# tx.net
KiCad netlist of a schematic drawn in EAGLE
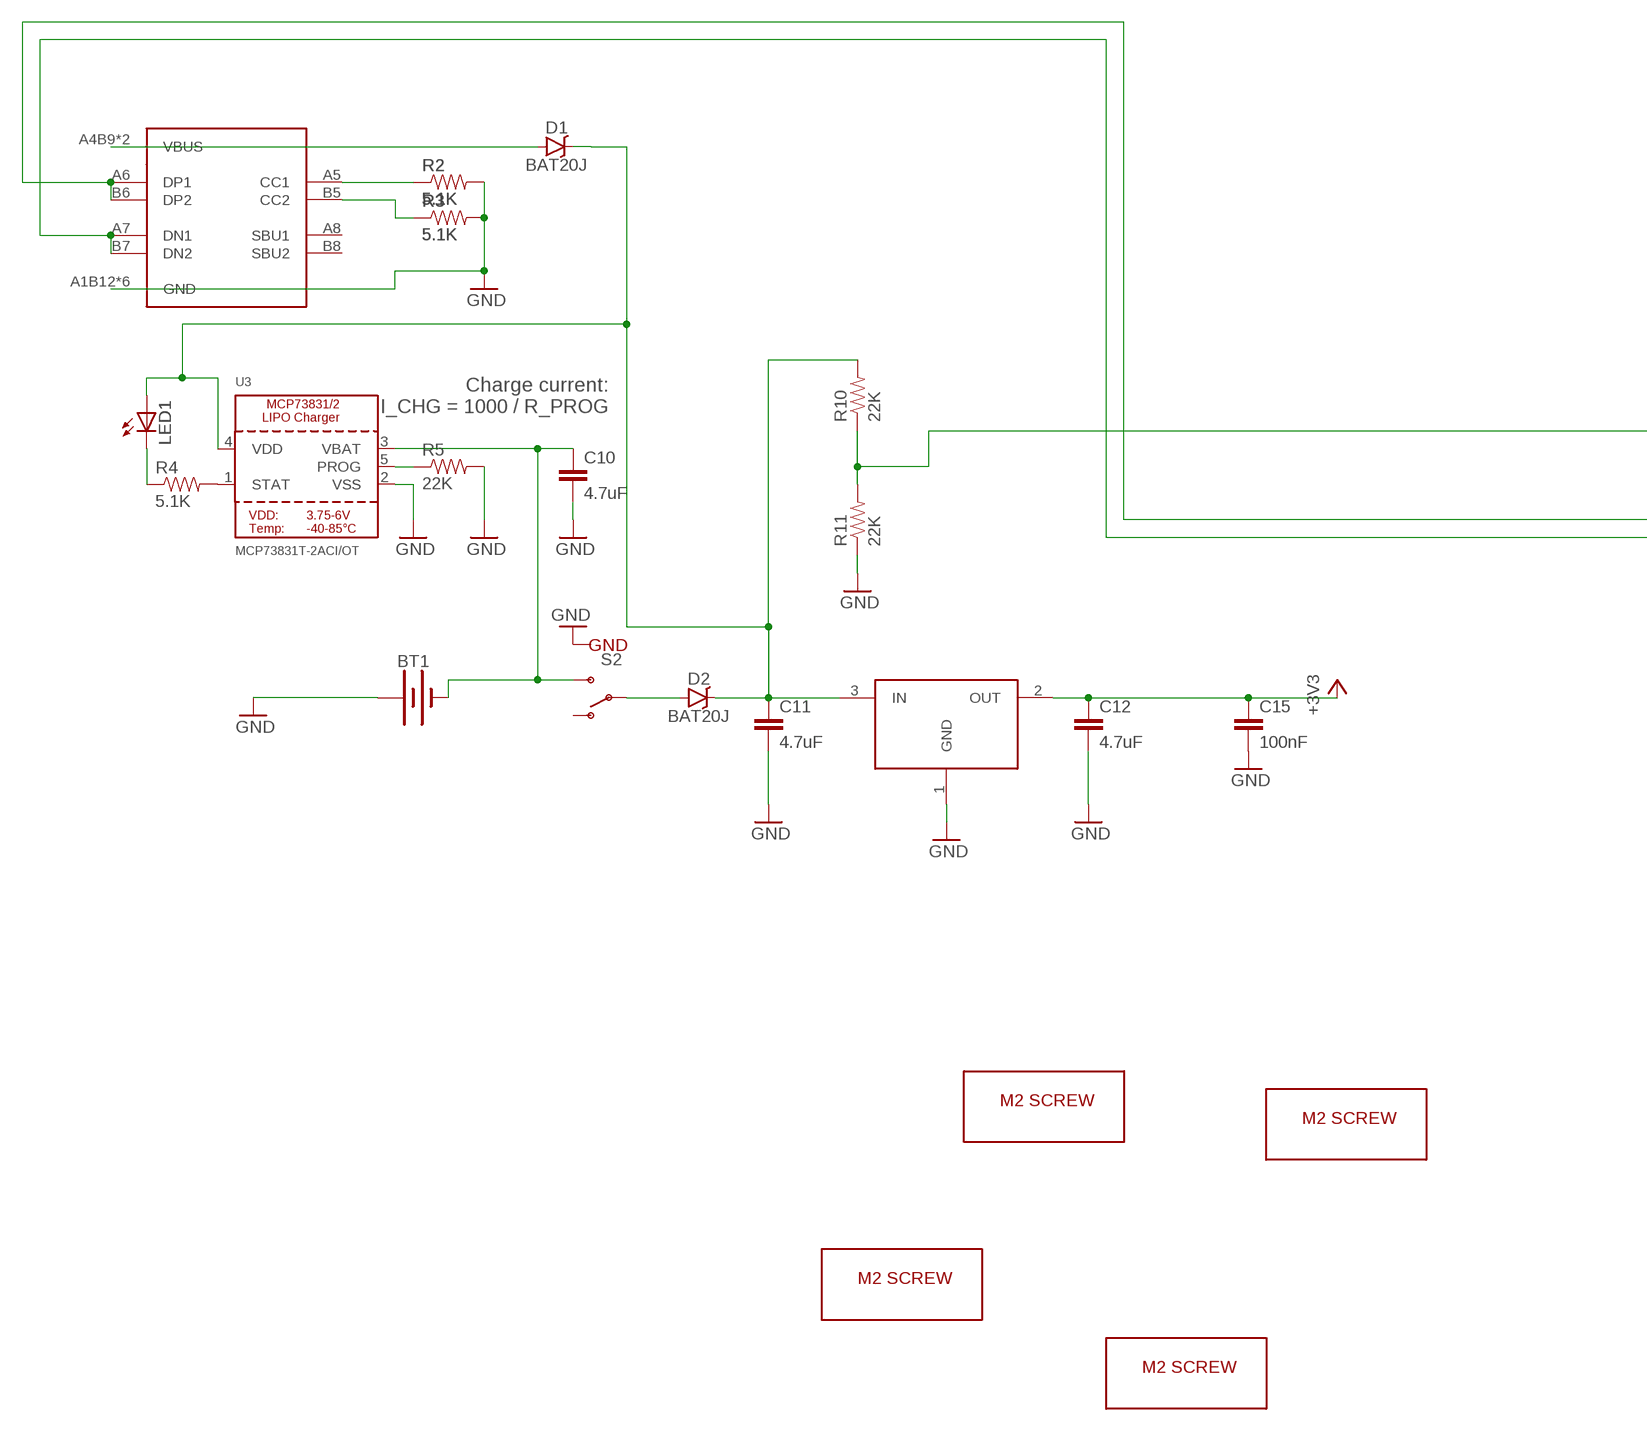
[diagram p0: schematic, sheet 1, part 1 of 2]
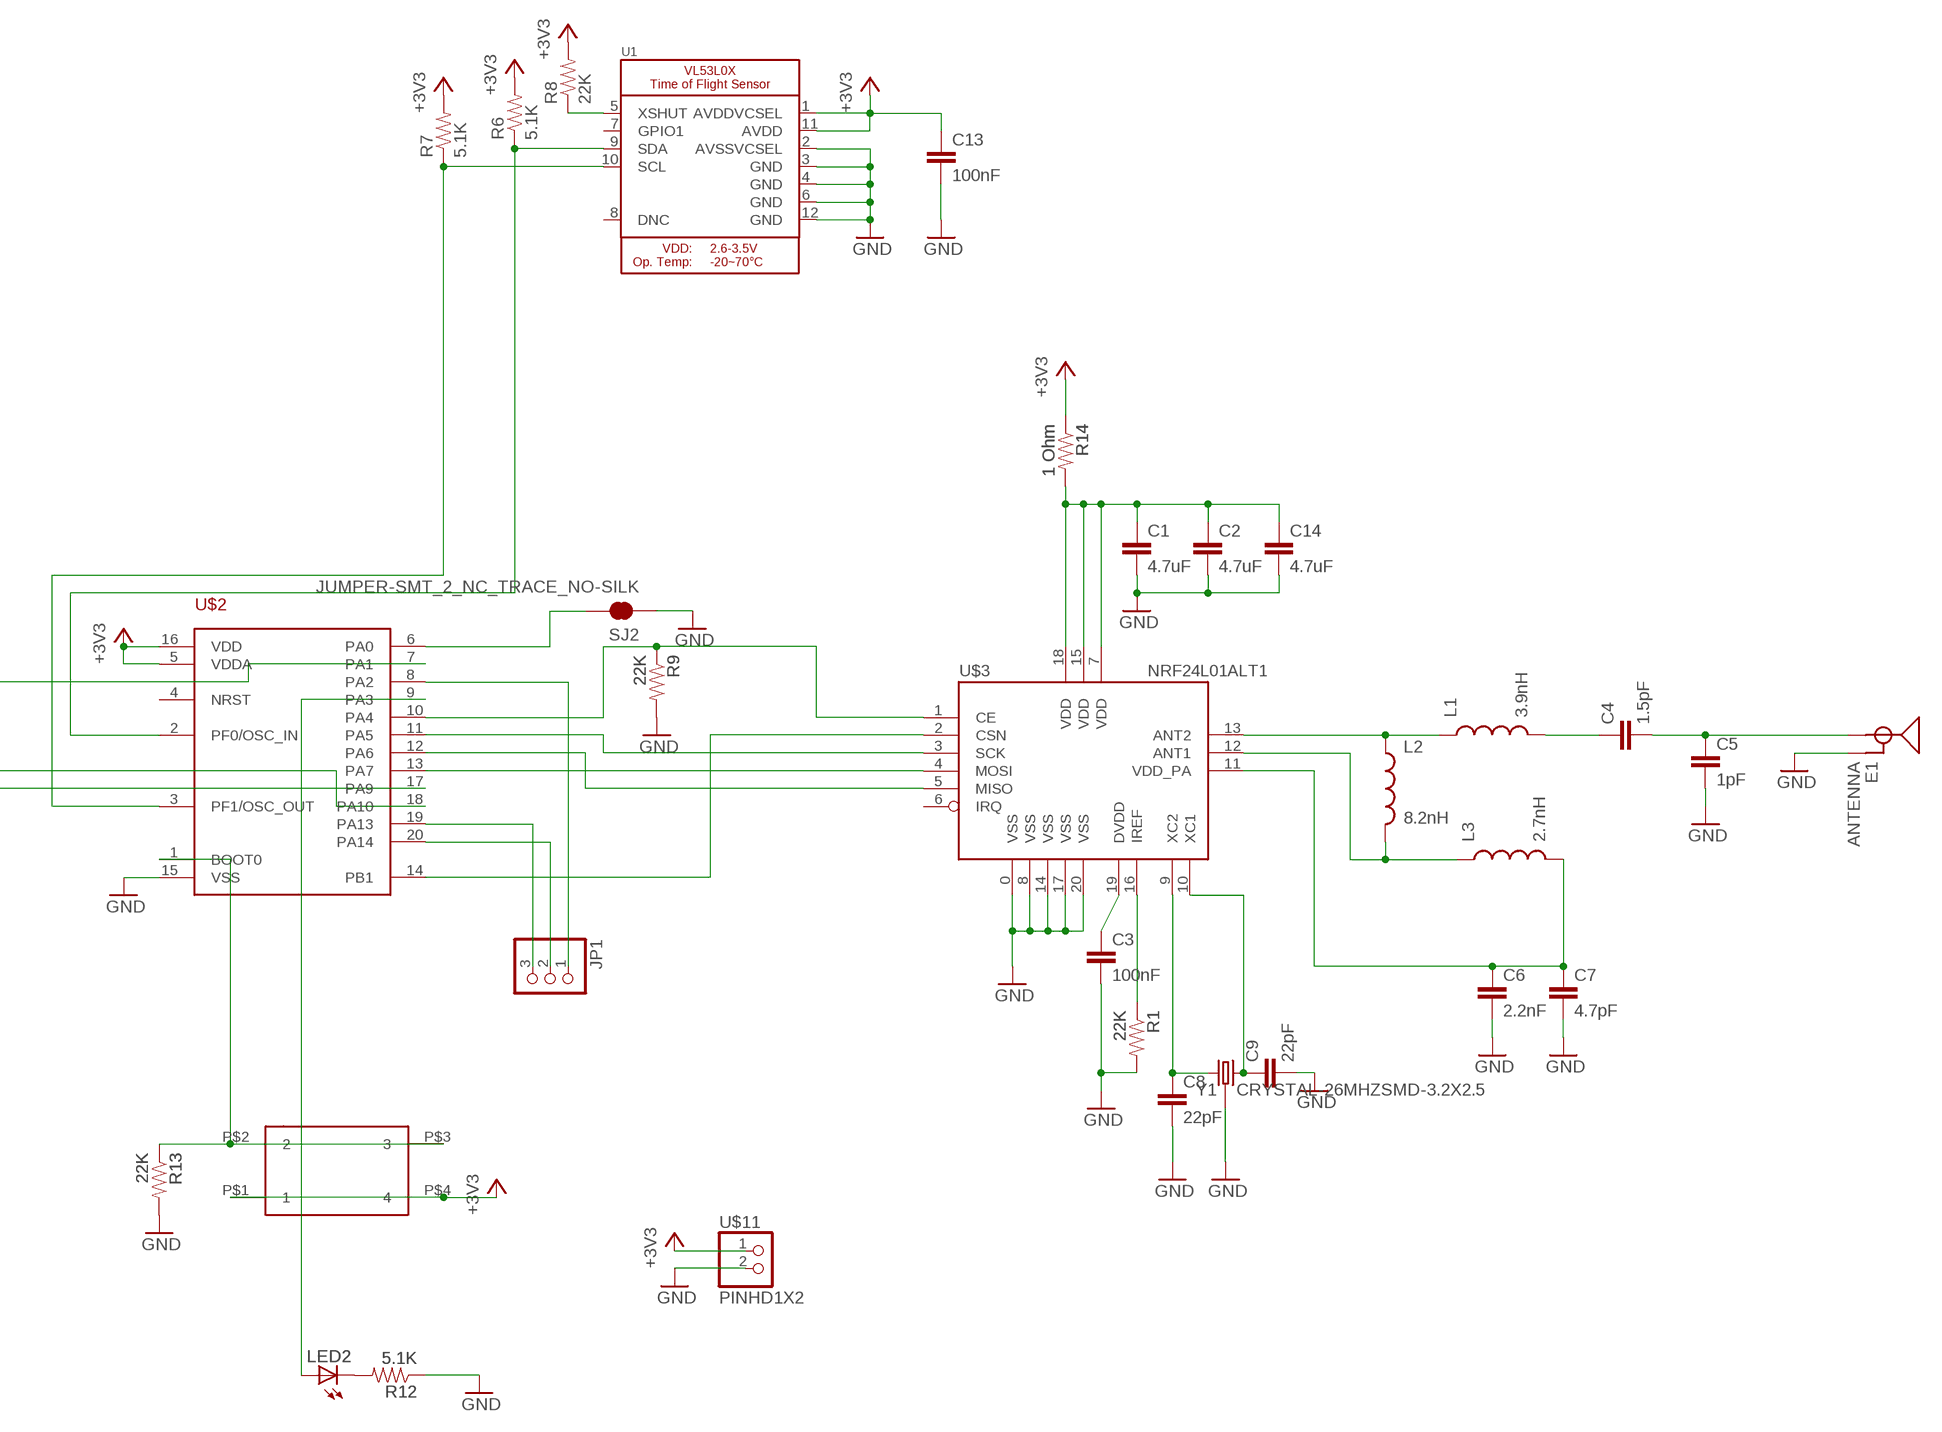
[diagram p1: schematic, sheet 1, part 2 of 2]

(export (version "E")
  (design (tool "Eeschema 10.0.6"))
  (components
    (comp (ref "BT1")
      (value "TX_SPARKFUN-BATTERIES_BATTERY-24.5MM_PTH")
      (footprint "eagle-import:TX_SPARKFUN-BATTERIES_BATTCON_24.5MM_PTH")
      (libsource (lib "eagle-import") (part "TX_SPARKFUN-BATTERIES_BATTERY-24.5MM_PTH"))
    )
    (comp (ref "C1")
      (value "4.7uF")
      (footprint "eagle-import:0805")
      (libsource (lib "eagle-import") (part "clock_CAP0805"))
    )
    (comp (ref "C2")
      (value "4.7uF")
      (footprint "eagle-import:0805")
      (libsource (lib "eagle-import") (part "clock_CAP0805"))
    )
    (comp (ref "C3")
      (value "100nF")
      (footprint "eagle-import:0805")
      (libsource (lib "eagle-import") (part "clock_CAP0805"))
    )
    (comp (ref "C4")
      (value "1.5pF")
      (footprint "eagle-import:0805")
      (libsource (lib "eagle-import") (part "clock_CAP0805"))
    )
    (comp (ref "C5")
      (value "1pF")
      (footprint "eagle-import:0805")
      (libsource (lib "eagle-import") (part "clock_CAP0805"))
    )
    (comp (ref "C6")
      (value "2.2nF")
      (footprint "eagle-import:0805")
      (libsource (lib "eagle-import") (part "clock_CAP0805"))
    )
    (comp (ref "C7")
      (value "4.7pF")
      (footprint "eagle-import:0805")
      (libsource (lib "eagle-import") (part "clock_CAP0805"))
    )
    (comp (ref "C8")
      (value "22pF")
      (footprint "eagle-import:0805")
      (libsource (lib "eagle-import") (part "clock_CAP0805"))
    )
    (comp (ref "C9")
      (value "22pF")
      (footprint "eagle-import:0805")
      (libsource (lib "eagle-import") (part "clock_CAP0805"))
    )
    (comp (ref "C10")
      (value "4.7uF")
      (footprint "eagle-import:0805")
      (libsource (lib "eagle-import") (part "CAP0805"))
    )
    (comp (ref "C11")
      (value "4.7uF")
      (footprint "eagle-import:0805")
      (libsource (lib "eagle-import") (part "clock_CAP0805"))
    )
    (comp (ref "C12")
      (value "4.7uF")
      (footprint "eagle-import:0805")
      (libsource (lib "eagle-import") (part "clock_CAP0805"))
    )
    (comp (ref "C13")
      (value "100nF")
      (footprint "eagle-import:0805")
      (libsource (lib "eagle-import") (part "clock_CAP0805"))
    )
    (comp (ref "C14")
      (value "4.7uF")
      (footprint "eagle-import:0805")
      (libsource (lib "eagle-import") (part "clock_CAP0805"))
    )
    (comp (ref "C15")
      (value "100nF")
      (footprint "eagle-import:0805")
      (libsource (lib "eagle-import") (part "clock_CAP0805"))
    )
    (comp (ref "D1")
      (value "BAT20J")
      (footprint "eagle-import:SOD-323")
      (libsource (lib "eagle-import") (part "DIODE-SCHOTTKY-BAT20J"))
    )
    (comp (ref "D2")
      (value "BAT20J")
      (footprint "eagle-import:SOD-323")
      (libsource (lib "eagle-import") (part "DIODE-SCHOTTKY-BAT20J"))
    )
    (comp (ref "E1")
      (value "ANTENNA")
      (footprint "eagle-import:TRACE_ANTENNA_2.4GHZ_25.7MM_TUNED")
      (libsource (lib "eagle-import") (part "ANTENNATRACE-TUNED"))
    )
    (comp (ref "JP1")
      (value "PINHD-1X3CB")
      (footprint "eagle-import:1X03-CLEANBIG")
      (libsource (lib "eagle-import") (part "PINHD-1X3CB"))
    )
    (comp (ref "L1")
      (value "3.9nH")
      (footprint "eagle-import:0805")
      (libsource (lib "eagle-import") (part "INDUCTOR0805"))
    )
    (comp (ref "L2")
      (value "8.2nH")
      (footprint "eagle-import:0805")
      (libsource (lib "eagle-import") (part "INDUCTOR0805"))
    )
    (comp (ref "L3")
      (value "2.7nH")
      (footprint "eagle-import:0805")
      (libsource (lib "eagle-import") (part "INDUCTOR0805"))
    )
    (comp (ref "LED1")
      (value "LEDCHIP-LED0805")
      (footprint "eagle-import:CHIP-LED0805")
      (libsource (lib "eagle-import") (part "LEDCHIP-LED0805"))
    )
    (comp (ref "LED2")
      (value "LEDCHIP-LED0805")
      (footprint "eagle-import:CHIP-LED0805")
      (libsource (lib "eagle-import") (part "LEDCHIP-LED0805"))
    )
    (comp (ref "R1")
      (value "22K")
      (footprint "eagle-import:0805")
      (libsource (lib "eagle-import") (part "joyAnalog_RESISTOR0805-RES"))
    )
    (comp (ref "R2")
      (value "5.1K")
      (footprint "eagle-import:0805")
      (libsource (lib "eagle-import") (part "joyAnalog_RESISTOR0805-RES"))
    )
    (comp (ref "R3")
      (value "5.1K")
      (footprint "eagle-import:0805")
      (libsource (lib "eagle-import") (part "joyAnalog_RESISTOR0805-RES"))
    )
    (comp (ref "R4")
      (value "5.1K")
      (footprint "eagle-import:0805")
      (libsource (lib "eagle-import") (part "RESISTOR0805-RES"))
    )
    (comp (ref "R5")
      (value "22K")
      (footprint "eagle-import:0805")
      (libsource (lib "eagle-import") (part "RESISTOR0805-RES"))
    )
    (comp (ref "R6")
      (value "5.1K")
      (footprint "eagle-import:0805")
      (libsource (lib "eagle-import") (part "RESISTOR0805-RES"))
    )
    (comp (ref "R7")
      (value "5.1K")
      (footprint "eagle-import:0805")
      (libsource (lib "eagle-import") (part "RESISTOR0805-RES"))
    )
    (comp (ref "R8")
      (value "22K")
      (footprint "eagle-import:0805")
      (libsource (lib "eagle-import") (part "RESISTOR0805-RES"))
    )
    (comp (ref "R9")
      (value "22K")
      (footprint "eagle-import:0805")
      (libsource (lib "eagle-import") (part "joyAnalog_RESISTOR0805-RES"))
    )
    (comp (ref "R10")
      (value "22K")
      (footprint "eagle-import:0805")
      (libsource (lib "eagle-import") (part "RESISTOR0805-RES"))
    )
    (comp (ref "R11")
      (value "22K")
      (footprint "eagle-import:0805")
      (libsource (lib "eagle-import") (part "RESISTOR0805-RES"))
    )
    (comp (ref "R12")
      (value "5.1K")
      (footprint "eagle-import:0805")
      (libsource (lib "eagle-import") (part "joyAnalog_RESISTOR0805-RES"))
    )
    (comp (ref "R13")
      (value "22K")
      (footprint "eagle-import:0805")
      (libsource (lib "eagle-import") (part "joyAnalog_RESISTOR0805-RES"))
    )
    (comp (ref "R14")
      (value "1 Ohm")
      (footprint "eagle-import:0805")
      (libsource (lib "eagle-import") (part "joyAnalog_RESISTOR0805-RES"))
    )
    (comp (ref "S2")
      (value "SWITCH-SPDTTDFGDFG")
      (footprint "eagle-import:SWITCH-SPST-SMD-A")
      (libsource (lib "eagle-import") (part "SWITCH-SPDTTDFGDFG"))
    )
    (comp (ref "SJ2")
      (value "JUMPER-SMT_2_NC_TRACE_NO-SILK")
      (footprint "eagle-import:SMT-JUMPER_2_NC_TRACE_NO-SILK")
      (libsource (lib "eagle-import") (part "JUMPER-SMT_2_NC_TRACE_NO-SILK"))
    )
    (comp (ref "U$1")
      (value "M2_SCREW_DEV")
      (footprint "eagle-import:M2_SCREW_FOOT")
      (libsource (lib "eagle-import") (part "M2_SCREW_DEV"))
    )
    (comp (ref "U$2")
      (value "STM32F030F4")
      (footprint "eagle-import:TSSOP20")
      (libsource (lib "eagle-import") (part "STM32F030F4"))
    )
    (comp (ref "U$3")
      (value "NRF24L01ALT1")
      (footprint "eagle-import:QFN20_ALT1")
      (libsource (lib "eagle-import") (part "NRF24L01ALT1"))
    )
    (comp (ref "U$4")
      (value "USBC_16P")
      (footprint "eagle-import:USBC_16P_FOOT")
      (libsource (lib "eagle-import") (part "USBC_16P"))
    )
    (comp (ref "U$9")
      (value "XC6206_DEV")
      (footprint "eagle-import:SOT23R_INFINEON")
      (libsource (lib "eagle-import") (part "XC6206_DEV"))
    )
    (comp (ref "U$10")
      (value "324_SW324_SWITCH_FOOT_HOLE")
      (footprint "eagle-import:342_SWICH_FOOT_HOLE")
      (libsource (lib "eagle-import") (part "324_SW324_SWITCH_FOOT_HOLE"))
    )
    (comp (ref "U$11")
      (value "PINHD1X2")
      (footprint "eagle-import:1X02")
      (libsource (lib "eagle-import") (part "PINHD1X2"))
    )
    (comp (ref "U$12")
      (value "M2_SCREW_DEV")
      (footprint "eagle-import:M2_SCREW_FOOT")
      (libsource (lib "eagle-import") (part "M2_SCREW_DEV"))
    )
    (comp (ref "U$13")
      (value "M2_SCREW_DEV")
      (footprint "eagle-import:M2_SCREW_FOOT")
      (libsource (lib "eagle-import") (part "M2_SCREW_DEV"))
    )
    (comp (ref "U$14")
      (value "M2_SCREW_DEV")
      (footprint "eagle-import:M2_SCREW_FOOT")
      (libsource (lib "eagle-import") (part "M2_SCREW_DEV"))
    )
    (comp (ref "U1")
      (value "VL53L0X")
      (footprint "eagle-import:LGA12_ST")
      (libsource (lib "eagle-import") (part "VL53L0X"))
    )
    (comp (ref "U3")
      (value "MCP73831T-2ACI/OT")
      (footprint "eagle-import:SOT23-5")
      (libsource (lib "eagle-import") (part "MCP73831/2"))
    )
    (comp (ref "Y1")
      (value "CRYSTAL-26MHZSMD-3.2X2.5")
      (footprint "eagle-import:CRYSTAL-SMD-3.2X2.5MM")
      (libsource (lib "eagle-import") (part "CRYSTAL-26MHZSMD-3.2X2.5"))
    )
  )
  (nets
    (net (code "1") (name "+3V3") (class "Default")
      (node (ref "C12") (pin "1") (pinfunction "1_1") (pintype "passive"))
      (node (ref "C13") (pin "1") (pinfunction "1_1") (pintype "passive"))
      (node (ref "C15") (pin "1") (pinfunction "1_1") (pintype "passive"))
      (node (ref "R14") (pin "1") (pinfunction "1_1") (pintype "passive"))
      (node (ref "R6") (pin "2") (pinfunction "2_2") (pintype "passive"))
      (node (ref "R7") (pin "2") (pinfunction "2_2") (pintype "passive"))
      (node (ref "R8") (pin "2") (pinfunction "2_2") (pintype "passive"))
      (node (ref "U$10") (pin "P$1") (pinfunction "1_P$1") (pintype "bidirectional"))
      (node (ref "U$10") (pin "P$4") (pinfunction "4_P$4") (pintype "bidirectional"))
      (node (ref "U$11") (pin "1") (pinfunction "1_1") (pintype "passive"))
      (node (ref "U$2") (pin "16") (pinfunction "VDD_16") (pintype "bidirectional"))
      (node (ref "U$2") (pin "5") (pinfunction "VDDA_5") (pintype "bidirectional"))
      (node (ref "U$9") (pin "2") (pinfunction "OUT_2") (pintype "bidirectional"))
      (node (ref "U1") (pin "1") (pinfunction "AVDDVCSEL_1") (pintype "power_in"))
      (node (ref "U1") (pin "11") (pinfunction "AVDD_11") (pintype "power_in"))
    )
    (net (code "2") (name "GND") (class "Default")
      (node (ref "BT1") (pin "2") (pinfunction "+_2") (pintype "power_in"))
      (node (ref "C1") (pin "2") (pinfunction "2_2") (pintype "passive"))
      (node (ref "C10") (pin "2") (pinfunction "2_2") (pintype "passive"))
      (node (ref "C11") (pin "2") (pinfunction "2_2") (pintype "passive"))
      (node (ref "C12") (pin "2") (pinfunction "2_2") (pintype "passive"))
      (node (ref "C13") (pin "2") (pinfunction "2_2") (pintype "passive"))
      (node (ref "C14") (pin "2") (pinfunction "2_2") (pintype "passive"))
      (node (ref "C15") (pin "2") (pinfunction "2_2") (pintype "passive"))
      (node (ref "C2") (pin "2") (pinfunction "2_2") (pintype "passive"))
      (node (ref "C3") (pin "2") (pinfunction "2_2") (pintype "passive"))
      (node (ref "C5") (pin "2") (pinfunction "2_2") (pintype "passive"))
      (node (ref "C6") (pin "2") (pinfunction "2_2") (pintype "passive"))
      (node (ref "C7") (pin "2") (pinfunction "2_2") (pintype "passive"))
      (node (ref "C8") (pin "2") (pinfunction "2_2") (pintype "passive"))
      (node (ref "C9") (pin "2") (pinfunction "2_2") (pintype "passive"))
      (node (ref "E1") (pin "GND") (pinfunction "GND_GND") (pintype "bidirectional"))
      (node (ref "E1") (pin "GND2") (pinfunction "GND_GND2") (pintype "bidirectional"))
      (node (ref "R1") (pin "2") (pinfunction "2_2") (pintype "passive"))
      (node (ref "R11") (pin "1") (pinfunction "1_1") (pintype "passive"))
      (node (ref "R12") (pin "1") (pinfunction "1_1") (pintype "passive"))
      (node (ref "R13") (pin "2") (pinfunction "2_2") (pintype "passive"))
      (node (ref "R2") (pin "2") (pinfunction "2_2") (pintype "passive"))
      (node (ref "R3") (pin "2") (pinfunction "2_2") (pintype "passive"))
      (node (ref "R5") (pin "2") (pinfunction "2_2") (pintype "passive"))
      (node (ref "R9") (pin "2") (pinfunction "2_2") (pintype "passive"))
      (node (ref "S2") (pin "G1") (pinfunction "GND_G1") (pintype "passive"))
      (node (ref "S2") (pin "G2") (pinfunction "GND_G2") (pintype "passive"))
      (node (ref "S2") (pin "G3") (pinfunction "GND_G3") (pintype "passive"))
      (node (ref "S2") (pin "G4") (pinfunction "GND_G4") (pintype "passive"))
      (node (ref "SJ2") (pin "1") (pinfunction "1_1") (pintype "passive"))
      (node (ref "U$11") (pin "2") (pinfunction "2_2") (pintype "passive"))
      (node (ref "U$2") (pin "15") (pinfunction "VSS_15") (pintype "bidirectional"))
      (node (ref "U$3") (pin "0") (pinfunction "VSS_0") (pintype "power_in"))
      (node (ref "U$3") (pin "14") (pinfunction "VSS_14") (pintype "power_in"))
      (node (ref "U$3") (pin "17") (pinfunction "VSS_17") (pintype "power_in"))
      (node (ref "U$3") (pin "20") (pinfunction "VSS_20") (pintype "power_in"))
      (node (ref "U$3") (pin "8") (pinfunction "VSS_8") (pintype "power_in"))
      (node (ref "U$4") (pin "A1B12") (pinfunction "GND_A1B12") (pintype "bidirectional"))
      (node (ref "U$4") (pin "B11A12") (pinfunction "GND_B11A12") (pintype "bidirectional"))
      (node (ref "U$4") (pin "P$13") (pinfunction "GND_P$13") (pintype "bidirectional"))
      (node (ref "U$4") (pin "P$14") (pinfunction "GND_P$14") (pintype "bidirectional"))
      (node (ref "U$4") (pin "P$15") (pinfunction "GND_P$15") (pintype "bidirectional"))
      (node (ref "U$4") (pin "P$16") (pinfunction "GND_P$16") (pintype "bidirectional"))
      (node (ref "U$9") (pin "1") (pinfunction "GND_1") (pintype "bidirectional"))
      (node (ref "U1") (pin "12") (pinfunction "GND_12") (pintype "power_in"))
      (node (ref "U1") (pin "2") (pinfunction "AVSSVCSEL_2") (pintype "power_in"))
      (node (ref "U1") (pin "3") (pinfunction "GND_3") (pintype "power_in"))
      (node (ref "U1") (pin "4") (pinfunction "GND_4") (pintype "power_in"))
      (node (ref "U1") (pin "6") (pinfunction "GND_6") (pintype "power_in"))
      (node (ref "U3") (pin "2") (pinfunction "VSS_2") (pintype "power_in"))
      (node (ref "Y1") (pin "2") (pinfunction "3_2") (pintype "passive"))
      (node (ref "Y1") (pin "4") (pinfunction "3_4") (pintype "passive"))
    )
    (net (code "3") (name "Net-(BT1--)") (class "Default")
      (node (ref "BT1") (pin "1") (pinfunction "-_1") (pintype "power_in"))
      (node (ref "C10") (pin "1") (pinfunction "1_1") (pintype "passive"))
      (node (ref "S2") (pin "3") (pinfunction "S_3") (pintype "passive"))
      (node (ref "U3") (pin "3") (pinfunction "VBAT_3") (pintype "power_in"))
    )
    (net (code "4") (name "Net-(C1-Pad1)") (class "Default")
      (node (ref "C1") (pin "1") (pinfunction "1_1") (pintype "passive"))
      (node (ref "C14") (pin "1") (pinfunction "1_1") (pintype "passive"))
      (node (ref "C2") (pin "1") (pinfunction "1_1") (pintype "passive"))
      (node (ref "R14") (pin "2") (pinfunction "2_2") (pintype "passive"))
      (node (ref "U$3") (pin "15") (pinfunction "VDD_15") (pintype "power_in"))
      (node (ref "U$3") (pin "18") (pinfunction "VDD_18") (pintype "power_in"))
      (node (ref "U$3") (pin "7") (pinfunction "VDD_7") (pintype "power_in"))
    )
    (net (code "5") (name "Net-(C4-Pad1)") (class "Default")
      (node (ref "C4") (pin "1") (pinfunction "1_1") (pintype "passive"))
      (node (ref "L1") (pin "2") (pinfunction "2_2") (pintype "passive"))
    )
    (net (code "6") (name "Net-(D1-PadA)") (class "Default")
      (node (ref "D1") (pin "A") (pinfunction "A_A") (pintype "passive"))
      (node (ref "U$4") (pin "A4B9") (pinfunction "VBUS_A4B9") (pintype "bidirectional"))
      (node (ref "U$4") (pin "B4A9") (pinfunction "VBUS_B4A9") (pintype "bidirectional"))
    )
    (net (code "7") (name "Net-(E1-SIGNAL)") (class "Default")
      (node (ref "C4") (pin "2") (pinfunction "2_2") (pintype "passive"))
      (node (ref "C5") (pin "1") (pinfunction "1_1") (pintype "passive"))
      (node (ref "E1") (pin "ANT") (pinfunction "SIGNAL_ANT") (pintype "bidirectional"))
    )
    (net (code "8") (name "Net-(LED1-PadC)") (class "Default")
      (node (ref "LED1") (pin "C") (pinfunction "C_C") (pintype "passive"))
      (node (ref "R4") (pin "1") (pinfunction "1_1") (pintype "passive"))
    )
    (net (code "9") (name "Net-(LED2-PadC)") (class "Default")
      (node (ref "LED2") (pin "C") (pinfunction "C_C") (pintype "passive"))
      (node (ref "R12") (pin "2") (pinfunction "2_2") (pintype "passive"))
    )
    (net (code "10") (name "Net-(S2-P)") (class "Default")
      (node (ref "D2") (pin "A") (pinfunction "A_A") (pintype "passive"))
      (node (ref "S2") (pin "2") (pinfunction "P_2") (pintype "passive"))
    )
    (net (code "11") (name "Net-(U$2-PA0)") (class "Default")
      (node (ref "SJ2") (pin "2") (pinfunction "2_2") (pintype "passive"))
      (node (ref "U$2") (pin "6") (pinfunction "PA0_6") (pintype "bidirectional"))
    )
    (net (code "12") (name "Net-(U$2-PA1)") (class "Default")
      (node (ref "R10") (pin "1") (pinfunction "1_1") (pintype "passive"))
      (node (ref "R11") (pin "2") (pinfunction "2_2") (pintype "passive"))
      (node (ref "U$2") (pin "7") (pinfunction "PA1_7") (pintype "bidirectional"))
    )
    (net (code "13") (name "Net-(U$2-PA2)") (class "Default")
      (node (ref "JP1") (pin "1") (pinfunction "1_1") (pintype "passive"))
      (node (ref "U$2") (pin "8") (pinfunction "PA2_8") (pintype "bidirectional"))
    )
    (net (code "14") (name "Net-(U$2-PA3)") (class "Default")
      (node (ref "LED2") (pin "A") (pinfunction "A_A") (pintype "passive"))
      (node (ref "U$2") (pin "9") (pinfunction "PA3_9") (pintype "bidirectional"))
    )
    (net (code "15") (name "Net-(U$2-PA4)") (class "Default")
      (node (ref "R9") (pin "1") (pinfunction "1_1") (pintype "passive"))
      (node (ref "U$2") (pin "10") (pinfunction "PA4_10") (pintype "bidirectional"))
      (node (ref "U$3") (pin "1") (pinfunction "CE_1") (pintype "input"))
    )
    (net (code "16") (name "Net-(U$2-PA5)") (class "Default")
      (node (ref "U$2") (pin "11") (pinfunction "PA5_11") (pintype "bidirectional"))
      (node (ref "U$3") (pin "3") (pinfunction "SCK_3") (pintype "input"))
    )
    (net (code "17") (name "Net-(U$2-PA6)") (class "Default")
      (node (ref "U$2") (pin "12") (pinfunction "PA6_12") (pintype "bidirectional"))
      (node (ref "U$3") (pin "5") (pinfunction "MISO_5") (pintype "output"))
    )
    (net (code "18") (name "Net-(U$2-PA7)") (class "Default")
      (node (ref "U$2") (pin "13") (pinfunction "PA7_13") (pintype "bidirectional"))
      (node (ref "U$3") (pin "4") (pinfunction "MOSI_4") (pintype "input"))
    )
    (net (code "19") (name "Net-(U$2-PA9)") (class "Default")
      (node (ref "U$2") (pin "17") (pinfunction "PA9_17") (pintype "bidirectional"))
      (node (ref "U$4") (pin "A7") (pinfunction "DN1_A7") (pintype "bidirectional"))
      (node (ref "U$4") (pin "B7") (pinfunction "DN2_B7") (pintype "bidirectional"))
    )
    (net (code "20") (name "Net-(U$2-PA10)") (class "Default")
      (node (ref "U$2") (pin "18") (pinfunction "PA10_18") (pintype "bidirectional"))
      (node (ref "U$4") (pin "A6") (pinfunction "DP1_A6") (pintype "bidirectional"))
      (node (ref "U$4") (pin "B6") (pinfunction "DP2_B6") (pintype "bidirectional"))
    )
    (net (code "21") (name "Net-(U$2-PA13)") (class "Default")
      (node (ref "JP1") (pin "3") (pinfunction "3_3") (pintype "passive"))
      (node (ref "U$2") (pin "19") (pinfunction "PA13_19") (pintype "bidirectional"))
    )
    (net (code "22") (name "Net-(U$2-PA14)") (class "Default")
      (node (ref "JP1") (pin "2") (pinfunction "2_2") (pintype "passive"))
      (node (ref "U$2") (pin "20") (pinfunction "PA14_20") (pintype "bidirectional"))
    )
    (net (code "23") (name "Net-(U$2-PB1)") (class "Default")
      (node (ref "U$2") (pin "14") (pinfunction "PB1_14") (pintype "bidirectional"))
      (node (ref "U$3") (pin "2") (pinfunction "CSN_2") (pintype "input"))
    )
    (net (code "24") (name "Net-(U$2-PF0{slash}OSC_IN)") (class "Default")
      (node (ref "R6") (pin "1") (pinfunction "1_1") (pintype "passive"))
      (node (ref "U$2") (pin "2") (pinfunction "PF0/OSC_IN_2") (pintype "bidirectional"))
      (node (ref "U1") (pin "9") (pinfunction "SDA_9") (pintype "open_collector"))
    )
    (net (code "25") (name "Net-(U$2-PF1{slash}OSC_OUT)") (class "Default")
      (node (ref "R7") (pin "1") (pinfunction "1_1") (pintype "passive"))
      (node (ref "U$2") (pin "3") (pinfunction "PF1/OSC_OUT_3") (pintype "bidirectional"))
      (node (ref "U1") (pin "10") (pinfunction "SCL_10") (pintype "open_collector"))
    )
    (net (code "26") (name "Net-(U$3-ANT1)") (class "Default")
      (node (ref "L2") (pin "2") (pinfunction "2_2") (pintype "passive"))
      (node (ref "L3") (pin "1") (pinfunction "1_1") (pintype "passive"))
      (node (ref "U$3") (pin "12") (pinfunction "ANT1_12") (pintype "output"))
    )
    (net (code "27") (name "Net-(U$3-ANT2)") (class "Default")
      (node (ref "L1") (pin "1") (pinfunction "1_1") (pintype "passive"))
      (node (ref "L2") (pin "1") (pinfunction "1_1") (pintype "passive"))
      (node (ref "U$3") (pin "13") (pinfunction "ANT2_13") (pintype "output"))
    )
    (net (code "28") (name "Net-(U$3-DVDD)") (class "Default")
      (node (ref "C3") (pin "1") (pinfunction "1_1") (pintype "passive"))
      (node (ref "U$3") (pin "19") (pinfunction "DVDD_19") (pintype "power_in"))
    )
    (net (code "29") (name "Net-(U$3-IREF)") (class "Default")
      (node (ref "R1") (pin "1") (pinfunction "1_1") (pintype "passive"))
      (node (ref "U$3") (pin "16") (pinfunction "IREF_16") (pintype "input"))
    )
    (net (code "30") (name "Net-(U$3-VDD_PA)") (class "Default")
      (node (ref "C6") (pin "1") (pinfunction "1_1") (pintype "passive"))
      (node (ref "C7") (pin "1") (pinfunction "1_1") (pintype "passive"))
      (node (ref "L3") (pin "2") (pinfunction "2_2") (pintype "passive"))
      (node (ref "U$3") (pin "11") (pinfunction "VDD_PA_11") (pintype "power_in"))
    )
    (net (code "31") (name "Net-(U$3-XC1)") (class "Default")
      (node (ref "C9") (pin "1") (pinfunction "1_1") (pintype "passive"))
      (node (ref "U$3") (pin "10") (pinfunction "XC1_10") (pintype "input"))
      (node (ref "Y1") (pin "3") (pinfunction "2_3") (pintype "passive"))
    )
    (net (code "32") (name "Net-(U$3-XC2)") (class "Default")
      (node (ref "C8") (pin "1") (pinfunction "1_1") (pintype "passive"))
      (node (ref "U$3") (pin "9") (pinfunction "XC2_9") (pintype "input"))
      (node (ref "Y1") (pin "1") (pinfunction "1_1") (pintype "passive"))
    )
    (net (code "33") (name "Net-(U$4-CC1)") (class "Default")
      (node (ref "R2") (pin "1") (pinfunction "1_1") (pintype "passive"))
      (node (ref "U$4") (pin "A5") (pinfunction "CC1_A5") (pintype "bidirectional"))
    )
    (net (code "34") (name "Net-(U$4-CC2)") (class "Default")
      (node (ref "R3") (pin "1") (pinfunction "1_1") (pintype "passive"))
      (node (ref "U$4") (pin "B5") (pinfunction "CC2_B5") (pintype "bidirectional"))
    )
    (net (code "35") (name "Net-(U$9-IN)") (class "Default")
      (node (ref "C11") (pin "1") (pinfunction "1_1") (pintype "passive"))
      (node (ref "D1") (pin "C") (pinfunction "C_C") (pintype "passive"))
      (node (ref "D2") (pin "C") (pinfunction "C_C") (pintype "passive"))
      (node (ref "LED1") (pin "A") (pinfunction "A_A") (pintype "passive"))
      (node (ref "R10") (pin "2") (pinfunction "2_2") (pintype "passive"))
      (node (ref "U$9") (pin "3") (pinfunction "IN_3") (pintype "bidirectional"))
      (node (ref "U3") (pin "4") (pinfunction "VDD_4") (pintype "power_in"))
    )
    (net (code "36") (name "Net-(U$10-2)") (class "Default")
      (node (ref "R13") (pin "1") (pinfunction "1_1") (pintype "passive"))
      (node (ref "U$10") (pin "P$2") (pinfunction "2_P$2") (pintype "bidirectional"))
      (node (ref "U$10") (pin "P$3") (pinfunction "3_P$3") (pintype "bidirectional"))
      (node (ref "U$2") (pin "1") (pinfunction "BOOT0_1") (pintype "bidirectional"))
    )
    (net (code "37") (name "Net-(U1-XSHUT)") (class "Default")
      (node (ref "R8") (pin "1") (pinfunction "1_1") (pintype "passive"))
      (node (ref "U1") (pin "5") (pinfunction "XSHUT_5") (pintype "input"))
    )
    (net (code "38") (name "Net-(U3-PROG)") (class "Default")
      (node (ref "R5") (pin "1") (pinfunction "1_1") (pintype "passive"))
      (node (ref "U3") (pin "5") (pinfunction "PROG_5") (pintype "input"))
    )
    (net (code "39") (name "Net-(U3-STAT)") (class "Default")
      (node (ref "R4") (pin "2") (pinfunction "2_2") (pintype "passive"))
      (node (ref "U3") (pin "1") (pinfunction "STAT_1") (pintype "output"))
    )
    (net (code "40") (name "unconnected-(S2-O-Pad1)") (class "Default")
      (node (ref "S2") (pin "1") (pinfunction "O_1") (pintype "passive"))
    )
    (net (code "41") (name "unconnected-(U$2-NRST-Pad4)") (class "Default")
      (node (ref "U$2") (pin "4") (pinfunction "NRST_4") (pintype "bidirectional"))
    )
    (net (code "42") (name "unconnected-(U$3-IRQ-Pad6)") (class "Default")
      (node (ref "U$3") (pin "6") (pinfunction "IRQ_6") (pintype "output"))
    )
    (net (code "43") (name "unconnected-(U$4-SBU1-PadA8)") (class "Default")
      (node (ref "U$4") (pin "A8") (pinfunction "SBU1_A8") (pintype "bidirectional"))
    )
    (net (code "44") (name "unconnected-(U$4-SBU2-PadB8)") (class "Default")
      (node (ref "U$4") (pin "B8") (pinfunction "SBU2_B8") (pintype "bidirectional"))
    )
    (net (code "45") (name "unconnected-(U1-DNC-Pad8)") (class "Default")
      (node (ref "U1") (pin "8") (pinfunction "DNC_8") (pintype "no_connect"))
    )
    (net (code "46") (name "unconnected-(U1-GPIO1-Pad7)") (class "Default")
      (node (ref "U1") (pin "7") (pinfunction "GPIO1_7") (pintype "output"))
    )
  )
)
